# MotorCellTwo.net
KiCad netlist of a schematic drawn in Altium Designer
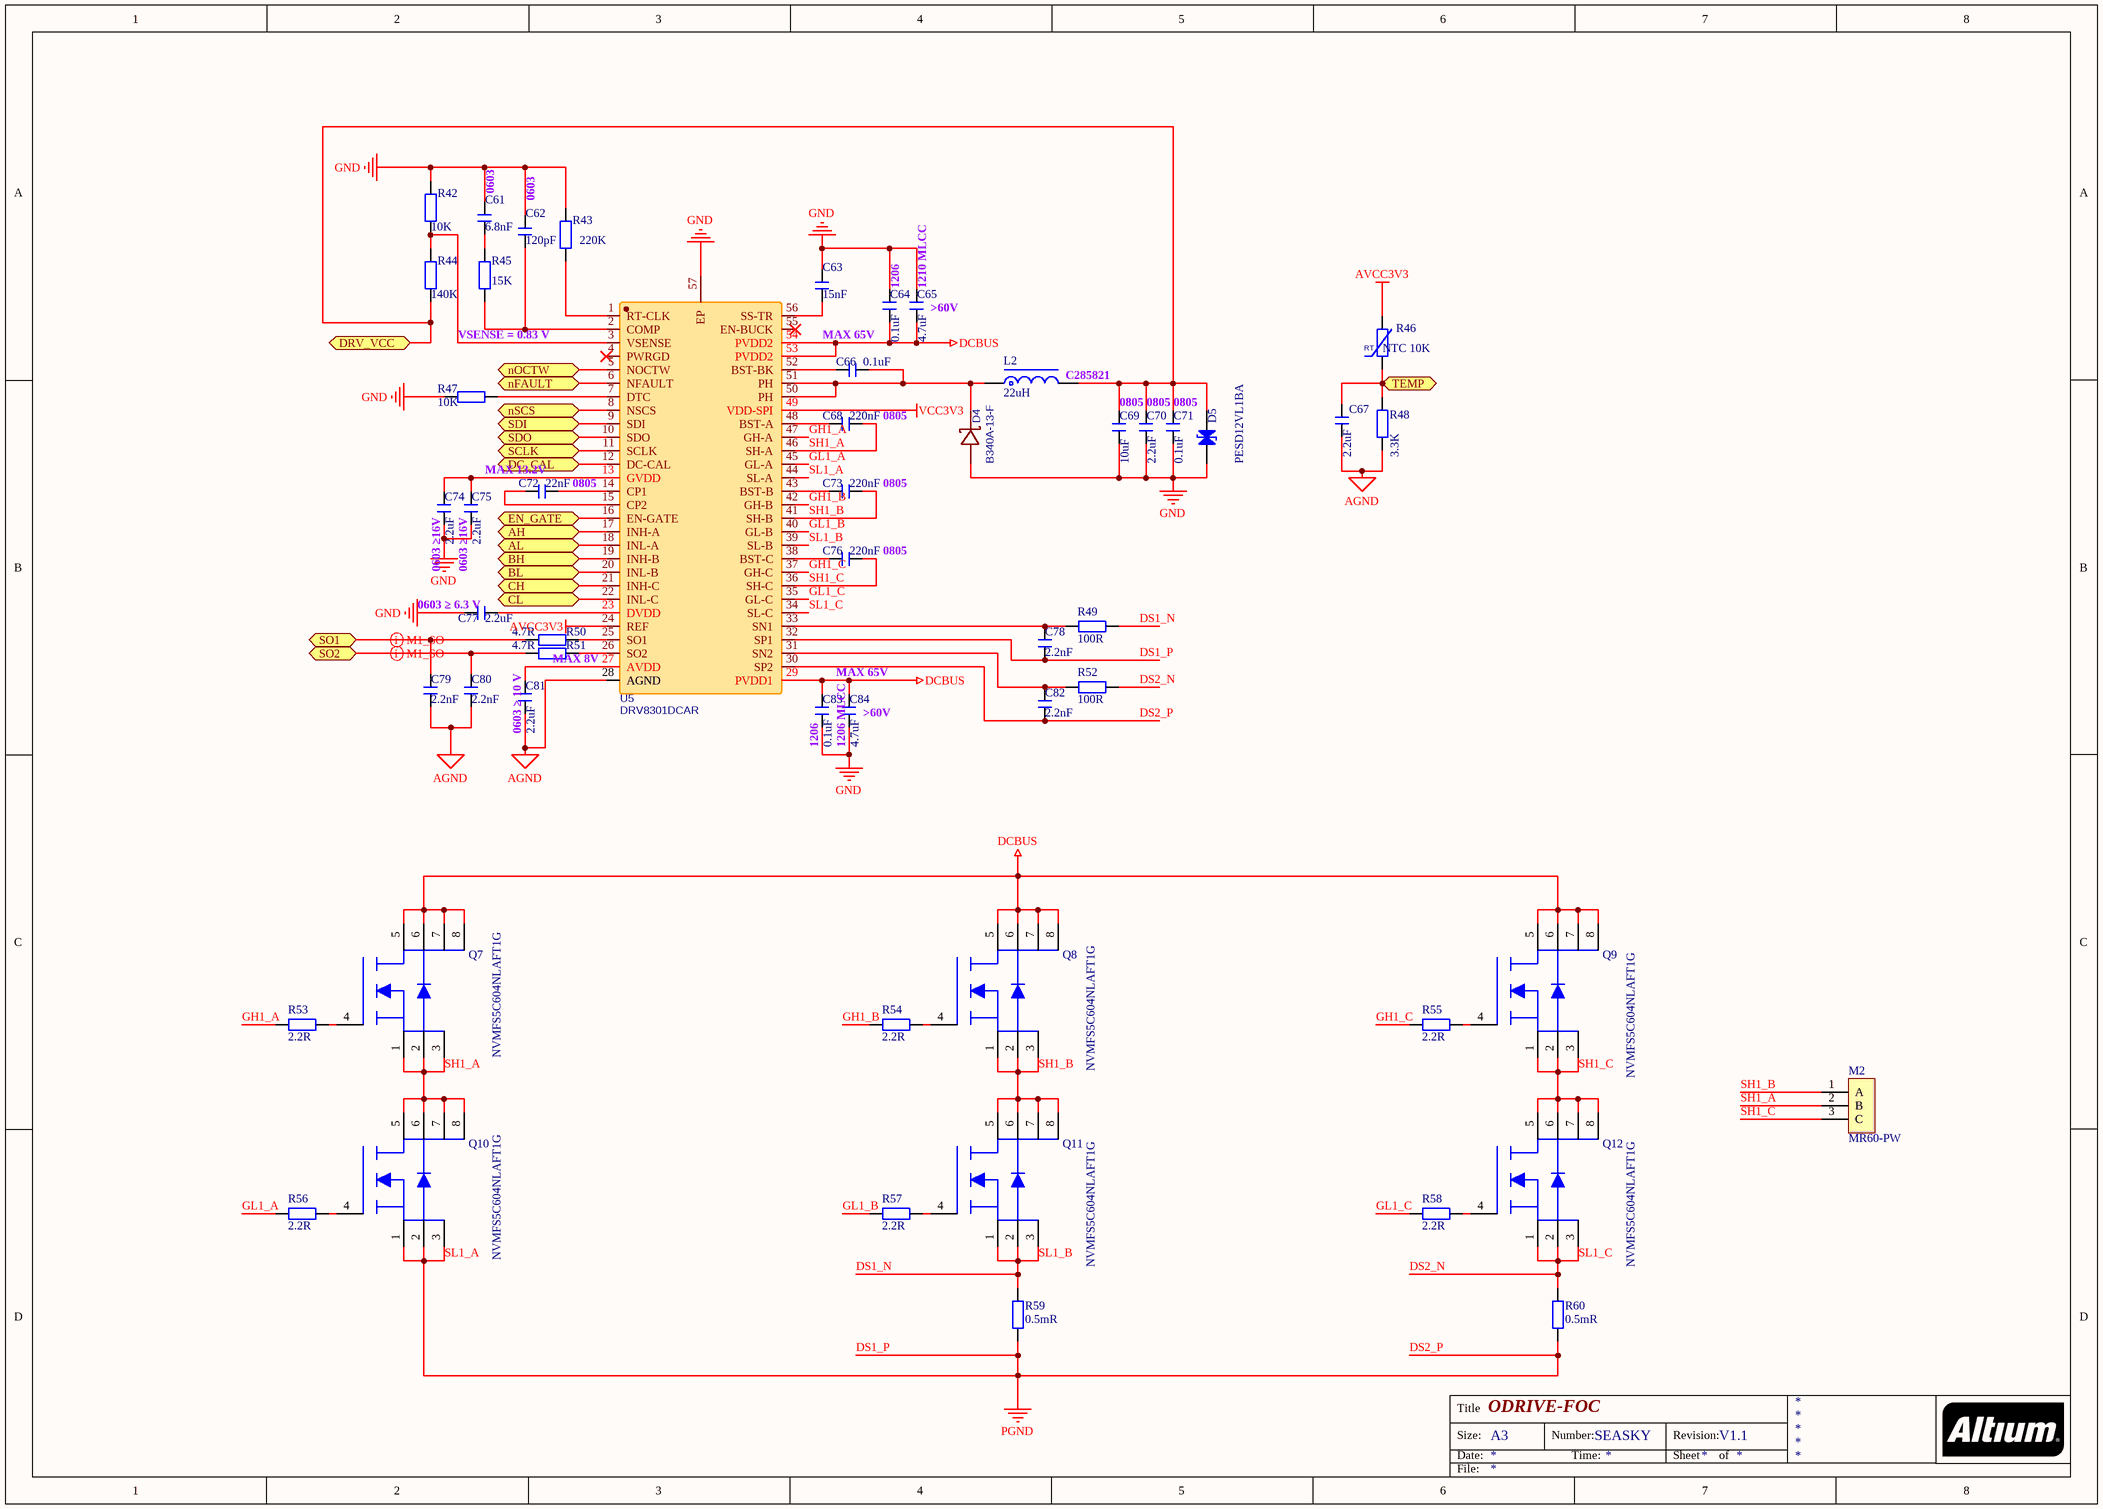
[diagram p0: MotorCellTwo.SchDoc]

(export (version "E")
  (design (tool "Eeschema 10.0.6"))
  (components
    (comp (ref "C61")
      (value "6.8nF")
      (footprint "C 0603_L")
      (description "贴片电容")
      (libsource (lib "0.1 - 电阻-电容-电感") (part "C"))
    )
    (comp (ref "C62")
      (value "120pF")
      (footprint "C 0603_L")
      (description "贴片电容")
      (libsource (lib "0.1 - 电阻-电容-电感") (part "C"))
    )
    (comp (ref "C63")
      (value "15nF")
      (footprint "C 0603_L")
      (description "贴片电容")
      (libsource (lib "0.1 - 电阻-电容-电感") (part "C"))
    )
    (comp (ref "C64")
      (value "0.1uF")
      (footprint "C 1206_L")
      (description "贴片电容")
      (libsource (lib "0.1 - 电阻-电容-电感") (part "C"))
    )
    (comp (ref "C65")
      (value "4.7uF")
      (footprint "C 1210_L")
      (description "贴片电容")
      (libsource (lib "0.1 - 电阻-电容-电感") (part "C"))
    )
    (comp (ref "C66")
      (value "0.1uF")
      (footprint "C 0603_L")
      (description "贴片电容")
      (libsource (lib "0.1 - 电阻-电容-电感") (part "C"))
    )
    (comp (ref "C67")
      (value "2.2uF")
      (footprint "C 0603_L")
      (description "贴片电容")
      (libsource (lib "0.1 - 电阻-电容-电感") (part "C"))
    )
    (comp (ref "C68")
      (value "220nF")
      (footprint "C 0805_L")
      (description "贴片电容")
      (libsource (lib "0.1 - 电阻-电容-电感") (part "C"))
    )
    (comp (ref "C69")
      (value "10uF")
      (footprint "C 0805_L")
      (description "贴片电容")
      (libsource (lib "0.1 - 电阻-电容-电感") (part "C"))
    )
    (comp (ref "C70")
      (value "2.2uF")
      (footprint "C 0805_L")
      (description "贴片电容")
      (libsource (lib "0.1 - 电阻-电容-电感") (part "C"))
    )
    (comp (ref "C71")
      (value "0.1uF")
      (footprint "C 0805_L")
      (description "贴片电容")
      (libsource (lib "0.1 - 电阻-电容-电感") (part "C"))
    )
    (comp (ref "C72")
      (value "22nF")
      (footprint "C 0805_L")
      (description "贴片电容")
      (libsource (lib "0.1 - 电阻-电容-电感") (part "C"))
    )
    (comp (ref "C73")
      (value "220nF")
      (footprint "C 0805_L")
      (description "贴片电容")
      (libsource (lib "0.1 - 电阻-电容-电感") (part "C"))
    )
    (comp (ref "C74")
      (value "2.2uF")
      (footprint "C 0603_L")
      (description "贴片电容")
      (libsource (lib "0.1 - 电阻-电容-电感") (part "C"))
    )
    (comp (ref "C75")
      (value "2.2uF")
      (footprint "C 0603_L")
      (description "贴片电容")
      (libsource (lib "0.1 - 电阻-电容-电感") (part "C"))
    )
    (comp (ref "C76")
      (value "220nF")
      (footprint "C 0805_L")
      (description "贴片电容")
      (libsource (lib "0.1 - 电阻-电容-电感") (part "C"))
    )
    (comp (ref "C77")
      (value "2.2uF")
      (footprint "C 0603_L")
      (description "贴片电容")
      (libsource (lib "0.1 - 电阻-电容-电感") (part "C"))
    )
    (comp (ref "C78")
      (value "2.2nF")
      (footprint "C 0603_L")
      (description "贴片电容")
      (libsource (lib "0.1 - 电阻-电容-电感") (part "C"))
    )
    (comp (ref "C79")
      (value "2.2nF")
      (footprint "C 0603_L")
      (description "贴片电容")
      (libsource (lib "0.1 - 电阻-电容-电感") (part "C"))
    )
    (comp (ref "C80")
      (value "2.2nF")
      (footprint "C 0603_L")
      (description "贴片电容")
      (libsource (lib "0.1 - 电阻-电容-电感") (part "C"))
    )
    (comp (ref "C81")
      (value "2.2uF")
      (footprint "C 0603_L")
      (description "贴片电容")
      (libsource (lib "0.1 - 电阻-电容-电感") (part "C"))
    )
    (comp (ref "C82")
      (value "2.2nF")
      (footprint "C 0603_L")
      (description "贴片电容")
      (libsource (lib "0.1 - 电阻-电容-电感") (part "C"))
    )
    (comp (ref "C83")
      (value "0.1uF")
      (footprint "C 1206_L")
      (description "贴片电容")
      (libsource (lib "0.1 - 电阻-电容-电感") (part "C"))
    )
    (comp (ref "C84")
      (value "4.7uF")
      (footprint "C 1210_L")
      (description "贴片电容")
      (libsource (lib "0.1 - 电阻-电容-电感") (part "C"))
    )
    (comp (ref "D4")
      (value "B340A-13-F")
      (footprint "SMA_L4.4-W2.6-LS5.0-RD")
      (fields (field (name "BOM_SUPPLIER PART") "C85098"))
      (libsource (lib "mx_pcb_library") (part "B340A-13-F"))
    )
    (comp (ref "D5")
      (value "PESD12VL1BA")
      (footprint "SOD-323")
      (description "PESD5V0S1BA、ESD二极管、5V")
      (libsource (lib "0.2 -  二极管-整流桥") (part "PESD5V0S1BA"))
    )
    (comp (ref "L2")
      (value "22uH")
      (footprint "CD53")
      (description "CD系列贴片线绕功率电感")
      (libsource (lib "0.1 - 电阻-电容-电感") (part "L-SMD"))
    )
    (comp (ref "M2")
      (value "MR60-PW")
      (footprint "MR30-PW")
      (libsource (lib "mx_pcb_library") (part "MR60-PW"))
    )
    (comp (ref "Q7")
      (value "NVMFS5C604NLAFT1G")
      (footprint "PG-TDSON-8_L5.0-W6.0-P1.27-LS6.2-BL-EP")
      (libsource (lib "mx_pcb_library") (part "BSC037N08NS5ATMA1"))
    )
    (comp (ref "Q8")
      (value "NVMFS5C604NLAFT1G")
      (footprint "PG-TDSON-8_L5.0-W6.0-P1.27-LS6.2-BL-EP")
      (libsource (lib "mx_pcb_library") (part "BSC037N08NS5ATMA1"))
    )
    (comp (ref "Q9")
      (value "NVMFS5C604NLAFT1G")
      (footprint "PG-TDSON-8_L5.0-W6.0-P1.27-LS6.2-BL-EP")
      (libsource (lib "mx_pcb_library") (part "BSC037N08NS5ATMA1"))
    )
    (comp (ref "Q10")
      (value "NVMFS5C604NLAFT1G")
      (footprint "PG-TDSON-8_L5.0-W6.0-P1.27-LS6.2-BL-EP")
      (libsource (lib "mx_pcb_library") (part "BSC037N08NS5ATMA1"))
    )
    (comp (ref "Q11")
      (value "NVMFS5C604NLAFT1G")
      (footprint "PG-TDSON-8_L5.0-W6.0-P1.27-LS6.2-BL-EP")
      (libsource (lib "mx_pcb_library") (part "BSC037N08NS5ATMA1"))
    )
    (comp (ref "Q12")
      (value "NVMFS5C604NLAFT1G")
      (footprint "PG-TDSON-8_L5.0-W6.0-P1.27-LS6.2-BL-EP")
      (libsource (lib "mx_pcb_library") (part "BSC037N08NS5ATMA1"))
    )
    (comp (ref "R42")
      (value "10K")
      (footprint "R 0603_L")
      (description "贴片电阻")
      (libsource (lib "0.1 - 电阻-电容-电感") (part "R"))
    )
    (comp (ref "R43")
      (value "220K")
      (footprint "R 0603_L")
      (description "贴片电阻")
      (libsource (lib "0.1 - 电阻-电容-电感") (part "R"))
    )
    (comp (ref "R44")
      (value "140K")
      (footprint "R 0603_L")
      (description "贴片电阻")
      (libsource (lib "0.1 - 电阻-电容-电感") (part "R"))
    )
    (comp (ref "R45")
      (value "15K")
      (footprint "R 0603_L")
      (description "贴片电阻")
      (libsource (lib "0.1 - 电阻-电容-电感") (part "R"))
    )
    (comp (ref "R46")
      (value "NTC 10K")
      (footprint "R 0805-HP_L")
      (description "热敏电阻")
      (libsource (lib "0.1 - 电阻-电容-电感") (part "RT"))
    )
    (comp (ref "R47")
      (value "10K")
      (footprint "R 0603_L")
      (description "贴片电阻")
      (libsource (lib "0.1 - 电阻-电容-电感") (part "R"))
    )
    (comp (ref "R48")
      (value "3.3K")
      (footprint "R 0805_L")
      (description "贴片电阻")
      (libsource (lib "0.1 - 电阻-电容-电感") (part "R"))
    )
    (comp (ref "R49")
      (value "100R")
      (footprint "R 0603_L")
      (description "贴片电阻")
      (libsource (lib "0.1 - 电阻-电容-电感") (part "R"))
    )
    (comp (ref "R50")
      (value "4.7R")
      (footprint "R 0603_L")
      (description "贴片电阻")
      (libsource (lib "0.1 - 电阻-电容-电感") (part "R"))
    )
    (comp (ref "R51")
      (value "4.7R")
      (footprint "R 0603_L")
      (description "贴片电阻")
      (libsource (lib "0.1 - 电阻-电容-电感") (part "R"))
    )
    (comp (ref "R52")
      (value "100R")
      (footprint "R 0603_L")
      (description "贴片电阻")
      (libsource (lib "0.1 - 电阻-电容-电感") (part "R"))
    )
    (comp (ref "R53")
      (value "2.2R")
      (footprint "R 0603_L")
      (description "贴片电阻")
      (libsource (lib "0.1 - 电阻-电容-电感") (part "R"))
    )
    (comp (ref "R54")
      (value "2.2R")
      (footprint "R 0603_L")
      (description "贴片电阻")
      (libsource (lib "0.1 - 电阻-电容-电感") (part "R"))
    )
    (comp (ref "R55")
      (value "2.2R")
      (footprint "R 0603_L")
      (description "贴片电阻")
      (libsource (lib "0.1 - 电阻-电容-电感") (part "R"))
    )
    (comp (ref "R56")
      (value "2.2R")
      (footprint "R 0603_L")
      (description "贴片电阻")
      (libsource (lib "0.1 - 电阻-电容-电感") (part "R"))
    )
    (comp (ref "R57")
      (value "2.2R")
      (footprint "R 0603_L")
      (description "贴片电阻")
      (libsource (lib "0.1 - 电阻-电容-电感") (part "R"))
    )
    (comp (ref "R58")
      (value "2.2R")
      (footprint "R 0603_L")
      (description "贴片电阻")
      (libsource (lib "0.1 - 电阻-电容-电感") (part "R"))
    )
    (comp (ref "R59")
      (value "0.5mR")
      (footprint "R3920")
      (description "精密贴片电阻")
      (libsource (lib "0.1 - 电阻-电容-电感") (part "R-Precision"))
    )
    (comp (ref "R60")
      (value "0.5mR")
      (footprint "R3920")
      (description "精密贴片电阻")
      (libsource (lib "0.1 - 电阻-电容-电感") (part "R-Precision"))
    )
    (comp (ref "U5")
      (value "DRV8301DCAR")
      (footprint "HTSSOP-56_L14.0-W6.0-P0.50-LS8.0-BL")
      (fields (field (name "BOM_SUPPLIER PART") "C98969") (field (name "CONTRIBUTOR") "LCSC"))
      (libsource (lib "mx_pcb_library") (part "DRV8301DCAR"))
    )
  )
  (nets
    (net (code "1") (name "/AH") (class "Default")
      (node (ref "U5") (pin "17") (pinfunction "INH-A_17") (pintype "passive"))
    )
    (net (code "2") (name "/AL") (class "Default")
      (node (ref "U5") (pin "18") (pinfunction "INL-A_18") (pintype "passive"))
    )
    (net (code "3") (name "/BH") (class "Default")
      (node (ref "U5") (pin "19") (pinfunction "INH-B_19") (pintype "passive"))
    )
    (net (code "4") (name "/BL") (class "Default")
      (node (ref "U5") (pin "20") (pinfunction "INL-B_20") (pintype "passive"))
    )
    (net (code "5") (name "/CH") (class "Default")
      (node (ref "U5") (pin "21") (pinfunction "INH-C_21") (pintype "passive"))
    )
    (net (code "6") (name "/CL") (class "Default")
      (node (ref "U5") (pin "22") (pinfunction "INL-C_22") (pintype "passive"))
    )
    (net (code "7") (name "/DC_CAL") (class "Default")
      (node (ref "U5") (pin "12") (pinfunction "DC-CAL_12") (pintype "passive"))
    )
    (net (code "8") (name "/DRV_VCC") (class "Default")
      (node (ref "C69") (pin "2") (pinfunction "2_2") (pintype "passive"))
      (node (ref "C70") (pin "2") (pinfunction "2_2") (pintype "passive"))
      (node (ref "C71") (pin "2") (pinfunction "2_2") (pintype "passive"))
      (node (ref "D5") (pin "1") (pinfunction "A_1") (pintype "passive"))
      (node (ref "L2") (pin "2") (pinfunction "2_2") (pintype "passive"))
      (node (ref "R44") (pin "1") (pinfunction "1_1") (pintype "passive"))
    )
    (net (code "9") (name "/DS1_N") (class "Default")
      (node (ref "Q11") (pin "1") (pinfunction "1_1") (pintype "passive"))
      (node (ref "Q11") (pin "2") (pinfunction "2_2") (pintype "passive"))
      (node (ref "Q11") (pin "3") (pinfunction "3_3") (pintype "passive"))
      (node (ref "R49") (pin "2") (pinfunction "2_2") (pintype "passive"))
      (node (ref "R59") (pin "2") (pinfunction "2_2") (pintype "passive"))
      (node (ref "U5") (pin "39") (pinfunction "SL-B_39") (pintype "passive"))
    )
    (net (code "10") (name "/DS2_N") (class "Default")
      (node (ref "Q12") (pin "1") (pinfunction "1_1") (pintype "passive"))
      (node (ref "Q12") (pin "2") (pinfunction "2_2") (pintype "passive"))
      (node (ref "Q12") (pin "3") (pinfunction "3_3") (pintype "passive"))
      (node (ref "R52") (pin "2") (pinfunction "2_2") (pintype "passive"))
      (node (ref "R60") (pin "2") (pinfunction "2_2") (pintype "passive"))
      (node (ref "U5") (pin "34") (pinfunction "SL-C_34") (pintype "passive"))
    )
    (net (code "11") (name "/EN_GATE") (class "Default")
      (node (ref "U5") (pin "16") (pinfunction "EN-GATE_16") (pintype "passive"))
    )
    (net (code "12") (name "/GH1_A") (class "Default")
      (node (ref "R53") (pin "1") (pinfunction "1_1") (pintype "passive"))
      (node (ref "U5") (pin "47") (pinfunction "GH-A_47") (pintype "passive"))
    )
    (net (code "13") (name "/GH1_B") (class "Default")
      (node (ref "R54") (pin "1") (pinfunction "1_1") (pintype "passive"))
      (node (ref "U5") (pin "42") (pinfunction "GH-B_42") (pintype "passive"))
    )
    (net (code "14") (name "/GH1_C") (class "Default")
      (node (ref "R55") (pin "1") (pinfunction "1_1") (pintype "passive"))
      (node (ref "U5") (pin "37") (pinfunction "GH-C_37") (pintype "passive"))
    )
    (net (code "15") (name "/GL1_A") (class "Default")
      (node (ref "R56") (pin "1") (pinfunction "1_1") (pintype "passive"))
      (node (ref "U5") (pin "45") (pinfunction "GL-A_45") (pintype "passive"))
    )
    (net (code "16") (name "/GL1_B") (class "Default")
      (node (ref "R57") (pin "1") (pinfunction "1_1") (pintype "passive"))
      (node (ref "U5") (pin "40") (pinfunction "GL-B_40") (pintype "passive"))
    )
    (net (code "17") (name "/GL1_C") (class "Default")
      (node (ref "R58") (pin "1") (pinfunction "1_1") (pintype "passive"))
      (node (ref "U5") (pin "35") (pinfunction "GL-C_35") (pintype "passive"))
    )
    (net (code "18") (name "/SCLK") (class "Default")
      (node (ref "U5") (pin "11") (pinfunction "SCLK_11") (pintype "passive"))
    )
    (net (code "19") (name "/SDI") (class "Default")
      (node (ref "U5") (pin "9") (pinfunction "SDI_9") (pintype "passive"))
    )
    (net (code "20") (name "/SDO") (class "Default")
      (node (ref "U5") (pin "10") (pinfunction "SDO_10") (pintype "passive"))
    )
    (net (code "21") (name "/SH1_A") (class "Default")
      (node (ref "C68") (pin "2") (pinfunction "2_2") (pintype "passive"))
      (node (ref "M2") (pin "2") (pinfunction "B_2") (pintype "passive"))
      (node (ref "Q10") (pin "5") (pinfunction "5_5") (pintype "passive"))
      (node (ref "Q10") (pin "6") (pinfunction "6_6") (pintype "passive"))
      (node (ref "Q10") (pin "7") (pinfunction "7_7") (pintype "passive"))
      (node (ref "Q10") (pin "8") (pinfunction "8_8") (pintype "passive"))
      (node (ref "Q7") (pin "1") (pinfunction "1_1") (pintype "passive"))
      (node (ref "Q7") (pin "2") (pinfunction "2_2") (pintype "passive"))
      (node (ref "Q7") (pin "3") (pinfunction "3_3") (pintype "passive"))
      (node (ref "U5") (pin "46") (pinfunction "SH-A_46") (pintype "passive"))
    )
    (net (code "22") (name "/SH1_B") (class "Default")
      (node (ref "C73") (pin "2") (pinfunction "2_2") (pintype "passive"))
      (node (ref "M2") (pin "1") (pinfunction "A_1") (pintype "passive"))
      (node (ref "Q11") (pin "5") (pinfunction "5_5") (pintype "passive"))
      (node (ref "Q11") (pin "6") (pinfunction "6_6") (pintype "passive"))
      (node (ref "Q11") (pin "7") (pinfunction "7_7") (pintype "passive"))
      (node (ref "Q11") (pin "8") (pinfunction "8_8") (pintype "passive"))
      (node (ref "Q8") (pin "1") (pinfunction "1_1") (pintype "passive"))
      (node (ref "Q8") (pin "2") (pinfunction "2_2") (pintype "passive"))
      (node (ref "Q8") (pin "3") (pinfunction "3_3") (pintype "passive"))
      (node (ref "U5") (pin "41") (pinfunction "SH-B_41") (pintype "passive"))
    )
    (net (code "23") (name "/SH1_C") (class "Default")
      (node (ref "C76") (pin "2") (pinfunction "2_2") (pintype "passive"))
      (node (ref "M2") (pin "3") (pinfunction "C_3") (pintype "passive"))
      (node (ref "Q12") (pin "5") (pinfunction "5_5") (pintype "passive"))
      (node (ref "Q12") (pin "6") (pinfunction "6_6") (pintype "passive"))
      (node (ref "Q12") (pin "7") (pinfunction "7_7") (pintype "passive"))
      (node (ref "Q12") (pin "8") (pinfunction "8_8") (pintype "passive"))
      (node (ref "Q9") (pin "1") (pinfunction "1_1") (pintype "passive"))
      (node (ref "Q9") (pin "2") (pinfunction "2_2") (pintype "passive"))
      (node (ref "Q9") (pin "3") (pinfunction "3_3") (pintype "passive"))
      (node (ref "U5") (pin "36") (pinfunction "SH-C_36") (pintype "passive"))
    )
    (net (code "24") (name "/SO1") (class "Default")
      (node (ref "C79") (pin "2") (pinfunction "2_2") (pintype "passive"))
      (node (ref "R50") (pin "1") (pinfunction "1_1") (pintype "passive"))
    )
    (net (code "25") (name "/SO2") (class "Default")
      (node (ref "C80") (pin "2") (pinfunction "2_2") (pintype "passive"))
      (node (ref "R51") (pin "1") (pinfunction "1_1") (pintype "passive"))
    )
    (net (code "26") (name "/TEMP") (class "Default")
      (node (ref "C67") (pin "1") (pinfunction "1_1") (pintype "passive"))
      (node (ref "R46") (pin "1") (pinfunction "1_1") (pintype "passive"))
      (node (ref "R48") (pin "2") (pinfunction "2_2") (pintype "passive"))
    )
    (net (code "27") (name "/nFAULT") (class "Default")
      (node (ref "U5") (pin "6") (pinfunction "NFAULT_6") (pintype "passive"))
    )
    (net (code "28") (name "/nOCTW") (class "Default")
      (node (ref "U5") (pin "5") (pinfunction "NOCTW_5") (pintype "passive"))
    )
    (net (code "29") (name "/nSCS") (class "Default")
      (node (ref "U5") (pin "8") (pinfunction "NSCS_8") (pintype "passive"))
    )
    (net (code "30") (name "AGND") (class "Default")
      (node (ref "C67") (pin "2") (pinfunction "2_2") (pintype "passive"))
      (node (ref "C79") (pin "1") (pinfunction "1_1") (pintype "passive"))
      (node (ref "C80") (pin "1") (pinfunction "1_1") (pintype "passive"))
      (node (ref "C81") (pin "1") (pinfunction "1_1") (pintype "passive"))
      (node (ref "R48") (pin "1") (pinfunction "1_1") (pintype "passive"))
      (node (ref "U5") (pin "28") (pinfunction "AGND_28") (pintype "passive"))
    )
    (net (code "31") (name "AVCC3V3") (class "Default")
      (node (ref "R46") (pin "2") (pinfunction "2_2") (pintype "passive"))
      (node (ref "U5") (pin "24") (pinfunction "REF_24") (pintype "passive"))
    )
    (net (code "32") (name "DCBUS") (class "Default")
      (node (ref "C64") (pin "1") (pinfunction "1_1") (pintype "passive"))
      (node (ref "C65") (pin "1") (pinfunction "1_1") (pintype "passive"))
      (node (ref "C83") (pin "2") (pinfunction "2_2") (pintype "passive"))
      (node (ref "C84") (pin "2") (pinfunction "2_2") (pintype "passive"))
      (node (ref "Q7") (pin "5") (pinfunction "5_5") (pintype "passive"))
      (node (ref "Q7") (pin "6") (pinfunction "6_6") (pintype "passive"))
      (node (ref "Q7") (pin "7") (pinfunction "7_7") (pintype "passive"))
      (node (ref "Q7") (pin "8") (pinfunction "8_8") (pintype "passive"))
      (node (ref "Q8") (pin "5") (pinfunction "5_5") (pintype "passive"))
      (node (ref "Q8") (pin "6") (pinfunction "6_6") (pintype "passive"))
      (node (ref "Q8") (pin "7") (pinfunction "7_7") (pintype "passive"))
      (node (ref "Q8") (pin "8") (pinfunction "8_8") (pintype "passive"))
      (node (ref "Q9") (pin "5") (pinfunction "5_5") (pintype "passive"))
      (node (ref "Q9") (pin "6") (pinfunction "6_6") (pintype "passive"))
      (node (ref "Q9") (pin "7") (pinfunction "7_7") (pintype "passive"))
      (node (ref "Q9") (pin "8") (pinfunction "8_8") (pintype "passive"))
      (node (ref "U5") (pin "29") (pinfunction "PVDD1_29") (pintype "passive"))
      (node (ref "U5") (pin "53") (pinfunction "PVDD2_53") (pintype "passive"))
      (node (ref "U5") (pin "54") (pinfunction "PVDD2_54") (pintype "passive"))
    )
    (net (code "33") (name "GND") (class "Default")
      (node (ref "C61") (pin "1") (pinfunction "1_1") (pintype "passive"))
      (node (ref "C62") (pin "1") (pinfunction "1_1") (pintype "passive"))
      (node (ref "C63") (pin "1") (pinfunction "1_1") (pintype "passive"))
      (node (ref "C64") (pin "2") (pinfunction "2_2") (pintype "passive"))
      (node (ref "C65") (pin "2") (pinfunction "2_2") (pintype "passive"))
      (node (ref "C69") (pin "1") (pinfunction "1_1") (pintype "passive"))
      (node (ref "C70") (pin "1") (pinfunction "1_1") (pintype "passive"))
      (node (ref "C71") (pin "1") (pinfunction "1_1") (pintype "passive"))
      (node (ref "C74") (pin "1") (pinfunction "1_1") (pintype "passive"))
      (node (ref "C75") (pin "1") (pinfunction "1_1") (pintype "passive"))
      (node (ref "C77") (pin "1") (pinfunction "1_1") (pintype "passive"))
      (node (ref "C83") (pin "1") (pinfunction "1_1") (pintype "passive"))
      (node (ref "C84") (pin "1") (pinfunction "1_1") (pintype "passive"))
      (node (ref "D4") (pin "2") (pinfunction "A_2") (pintype "passive"))
      (node (ref "D5") (pin "2") (pinfunction "K_2") (pintype "passive"))
      (node (ref "R42") (pin "2") (pinfunction "2_2") (pintype "passive"))
      (node (ref "R43") (pin "2") (pinfunction "2_2") (pintype "passive"))
      (node (ref "R47") (pin "2") (pinfunction "2_2") (pintype "passive"))
      (node (ref "U5") (pin "57") (pinfunction "EP_57") (pintype "passive"))
    )
    (net (code "34") (name "Net-(C61-Pad2)") (class "Default")
      (node (ref "C61") (pin "2") (pinfunction "2_2") (pintype "passive"))
      (node (ref "R45") (pin "2") (pinfunction "2_2") (pintype "passive"))
    )
    (net (code "35") (name "Net-(D4-K)") (class "Default")
      (node (ref "C66") (pin "1") (pinfunction "1_1") (pintype "passive"))
      (node (ref "D4") (pin "1") (pinfunction "K_1") (pintype "passive"))
      (node (ref "L2") (pin "1") (pinfunction "1_1") (pintype "passive"))
      (node (ref "U5") (pin "50") (pinfunction "PH_50") (pintype "passive"))
      (node (ref "U5") (pin "51") (pinfunction "PH_51") (pintype "passive"))
    )
    (net (code "36") (name "Net-(Q7-Pad4)") (class "Default")
      (node (ref "Q7") (pin "4") (pinfunction "4_4") (pintype "passive"))
      (node (ref "R53") (pin "2") (pinfunction "2_2") (pintype "passive"))
    )
    (net (code "37") (name "Net-(Q8-Pad4)") (class "Default")
      (node (ref "Q8") (pin "4") (pinfunction "4_4") (pintype "passive"))
      (node (ref "R54") (pin "2") (pinfunction "2_2") (pintype "passive"))
    )
    (net (code "38") (name "Net-(Q9-Pad4)") (class "Default")
      (node (ref "Q9") (pin "4") (pinfunction "4_4") (pintype "passive"))
      (node (ref "R55") (pin "2") (pinfunction "2_2") (pintype "passive"))
    )
    (net (code "39") (name "Net-(Q10-Pad4)") (class "Default")
      (node (ref "Q10") (pin "4") (pinfunction "4_4") (pintype "passive"))
      (node (ref "R56") (pin "2") (pinfunction "2_2") (pintype "passive"))
    )
    (net (code "40") (name "Net-(Q11-Pad4)") (class "Default")
      (node (ref "Q11") (pin "4") (pinfunction "4_4") (pintype "passive"))
      (node (ref "R57") (pin "2") (pinfunction "2_2") (pintype "passive"))
    )
    (net (code "41") (name "Net-(Q12-Pad4)") (class "Default")
      (node (ref "Q12") (pin "4") (pinfunction "4_4") (pintype "passive"))
      (node (ref "R58") (pin "2") (pinfunction "2_2") (pintype "passive"))
    )
    (net (code "42") (name "Net-(U5-AVDD)") (class "Default")
      (node (ref "C81") (pin "2") (pinfunction "2_2") (pintype "passive"))
      (node (ref "U5") (pin "27") (pinfunction "AVDD_27") (pintype "passive"))
    )
    (net (code "43") (name "Net-(U5-BST-A)") (class "Default")
      (node (ref "C68") (pin "1") (pinfunction "1_1") (pintype "passive"))
      (node (ref "U5") (pin "48") (pinfunction "BST-A_48") (pintype "passive"))
    )
    (net (code "44") (name "Net-(U5-BST-B)") (class "Default")
      (node (ref "C73") (pin "1") (pinfunction "1_1") (pintype "passive"))
      (node (ref "U5") (pin "43") (pinfunction "BST-B_43") (pintype "passive"))
    )
    (net (code "45") (name "Net-(U5-BST-BK)") (class "Default")
      (node (ref "C66") (pin "2") (pinfunction "2_2") (pintype "passive"))
      (node (ref "U5") (pin "52") (pinfunction "BST-BK_52") (pintype "passive"))
    )
    (net (code "46") (name "Net-(U5-BST-C)") (class "Default")
      (node (ref "C76") (pin "1") (pinfunction "1_1") (pintype "passive"))
      (node (ref "U5") (pin "38") (pinfunction "BST-C_38") (pintype "passive"))
    )
    (net (code "47") (name "Net-(U5-COMP)") (class "Default")
      (node (ref "C62") (pin "2") (pinfunction "2_2") (pintype "passive"))
      (node (ref "R45") (pin "1") (pinfunction "1_1") (pintype "passive"))
      (node (ref "U5") (pin "2") (pinfunction "COMP_2") (pintype "passive"))
    )
    (net (code "48") (name "Net-(U5-CP1)") (class "Default")
      (node (ref "C72") (pin "1") (pinfunction "1_1") (pintype "passive"))
      (node (ref "U5") (pin "14") (pinfunction "CP1_14") (pintype "passive"))
    )
    (net (code "49") (name "Net-(U5-CP2)") (class "Default")
      (node (ref "C72") (pin "2") (pinfunction "2_2") (pintype "passive"))
      (node (ref "U5") (pin "15") (pinfunction "CP2_15") (pintype "passive"))
    )
    (net (code "50") (name "Net-(U5-DTC)") (class "Default")
      (node (ref "R47") (pin "1") (pinfunction "1_1") (pintype "passive"))
      (node (ref "U5") (pin "7") (pinfunction "DTC_7") (pintype "passive"))
    )
    (net (code "51") (name "Net-(U5-DVDD)") (class "Default")
      (node (ref "C77") (pin "2") (pinfunction "2_2") (pintype "passive"))
      (node (ref "U5") (pin "23") (pinfunction "DVDD_23") (pintype "passive"))
    )
    (net (code "52") (name "Net-(U5-GVDD)") (class "Default")
      (node (ref "C74") (pin "2") (pinfunction "2_2") (pintype "passive"))
      (node (ref "C75") (pin "2") (pinfunction "2_2") (pintype "passive"))
      (node (ref "U5") (pin "13") (pinfunction "GVDD_13") (pintype "passive"))
    )
    (net (code "53") (name "Net-(U5-RT-CLK)") (class "Default")
      (node (ref "R43") (pin "1") (pinfunction "1_1") (pintype "passive"))
      (node (ref "U5") (pin "1") (pinfunction "RT-CLK_1") (pintype "passive"))
    )
    (net (code "54") (name "Net-(U5-SN1)") (class "Default")
      (node (ref "C78") (pin "2") (pinfunction "2_2") (pintype "passive"))
      (node (ref "R49") (pin "1") (pinfunction "1_1") (pintype "passive"))
      (node (ref "U5") (pin "33") (pinfunction "SN1_33") (pintype "passive"))
    )
    (net (code "55") (name "Net-(U5-SN2)") (class "Default")
      (node (ref "C82") (pin "2") (pinfunction "2_2") (pintype "passive"))
      (node (ref "R52") (pin "1") (pinfunction "1_1") (pintype "passive"))
      (node (ref "U5") (pin "31") (pinfunction "SN2_31") (pintype "passive"))
    )
    (net (code "56") (name "Net-(U5-SO1)") (class "Default")
      (node (ref "R50") (pin "2") (pinfunction "2_2") (pintype "passive"))
      (node (ref "U5") (pin "25") (pinfunction "SO1_25") (pintype "passive"))
    )
    (net (code "57") (name "Net-(U5-SO2)") (class "Default")
      (node (ref "R51") (pin "2") (pinfunction "2_2") (pintype "passive"))
      (node (ref "U5") (pin "26") (pinfunction "SO2_26") (pintype "passive"))
    )
    (net (code "58") (name "Net-(U5-SS-TR)") (class "Default")
      (node (ref "C63") (pin "2") (pinfunction "2_2") (pintype "passive"))
      (node (ref "U5") (pin "56") (pinfunction "SS-TR_56") (pintype "passive"))
    )
    (net (code "59") (name "Net-(U5-VSENSE)") (class "Default")
      (node (ref "R42") (pin "1") (pinfunction "1_1") (pintype "passive"))
      (node (ref "R44") (pin "2") (pinfunction "2_2") (pintype "passive"))
      (node (ref "U5") (pin "3") (pinfunction "VSENSE_3") (pintype "passive"))
    )
    (net (code "60") (name "PGND") (class "Default")
      (node (ref "C78") (pin "1") (pinfunction "1_1") (pintype "passive"))
      (node (ref "C82") (pin "1") (pinfunction "1_1") (pintype "passive"))
      (node (ref "Q10") (pin "1") (pinfunction "1_1") (pintype "passive"))
      (node (ref "Q10") (pin "2") (pinfunction "2_2") (pintype "passive"))
      (node (ref "Q10") (pin "3") (pinfunction "3_3") (pintype "passive"))
      (node (ref "R59") (pin "1") (pinfunction "1_1") (pintype "passive"))
      (node (ref "R60") (pin "1") (pinfunction "1_1") (pintype "passive"))
      (node (ref "U5") (pin "30") (pinfunction "SP2_30") (pintype "passive"))
      (node (ref "U5") (pin "32") (pinfunction "SP1_32") (pintype "passive"))
      (node (ref "U5") (pin "44") (pinfunction "SL-A_44") (pintype "passive"))
    )
    (net (code "61") (name "VCC3V3") (class "Default")
      (node (ref "U5") (pin "49") (pinfunction "VDD-SPI_49") (pintype "passive"))
    )
    (net (code "62") (name "unconnected-(U5-EN-BUCK-Pad55)") (class "Default")
      (node (ref "U5") (pin "55") (pinfunction "EN-BUCK_55") (pintype "passive+no_connect"))
    )
    (net (code "63") (name "unconnected-(U5-PWRGD-Pad4)") (class "Default")
      (node (ref "U5") (pin "4") (pinfunction "PWRGD_4") (pintype "passive+no_connect"))
    )
  )
)
